# MISC.net
KiCad netlist of a schematic drawn in Altium Designer
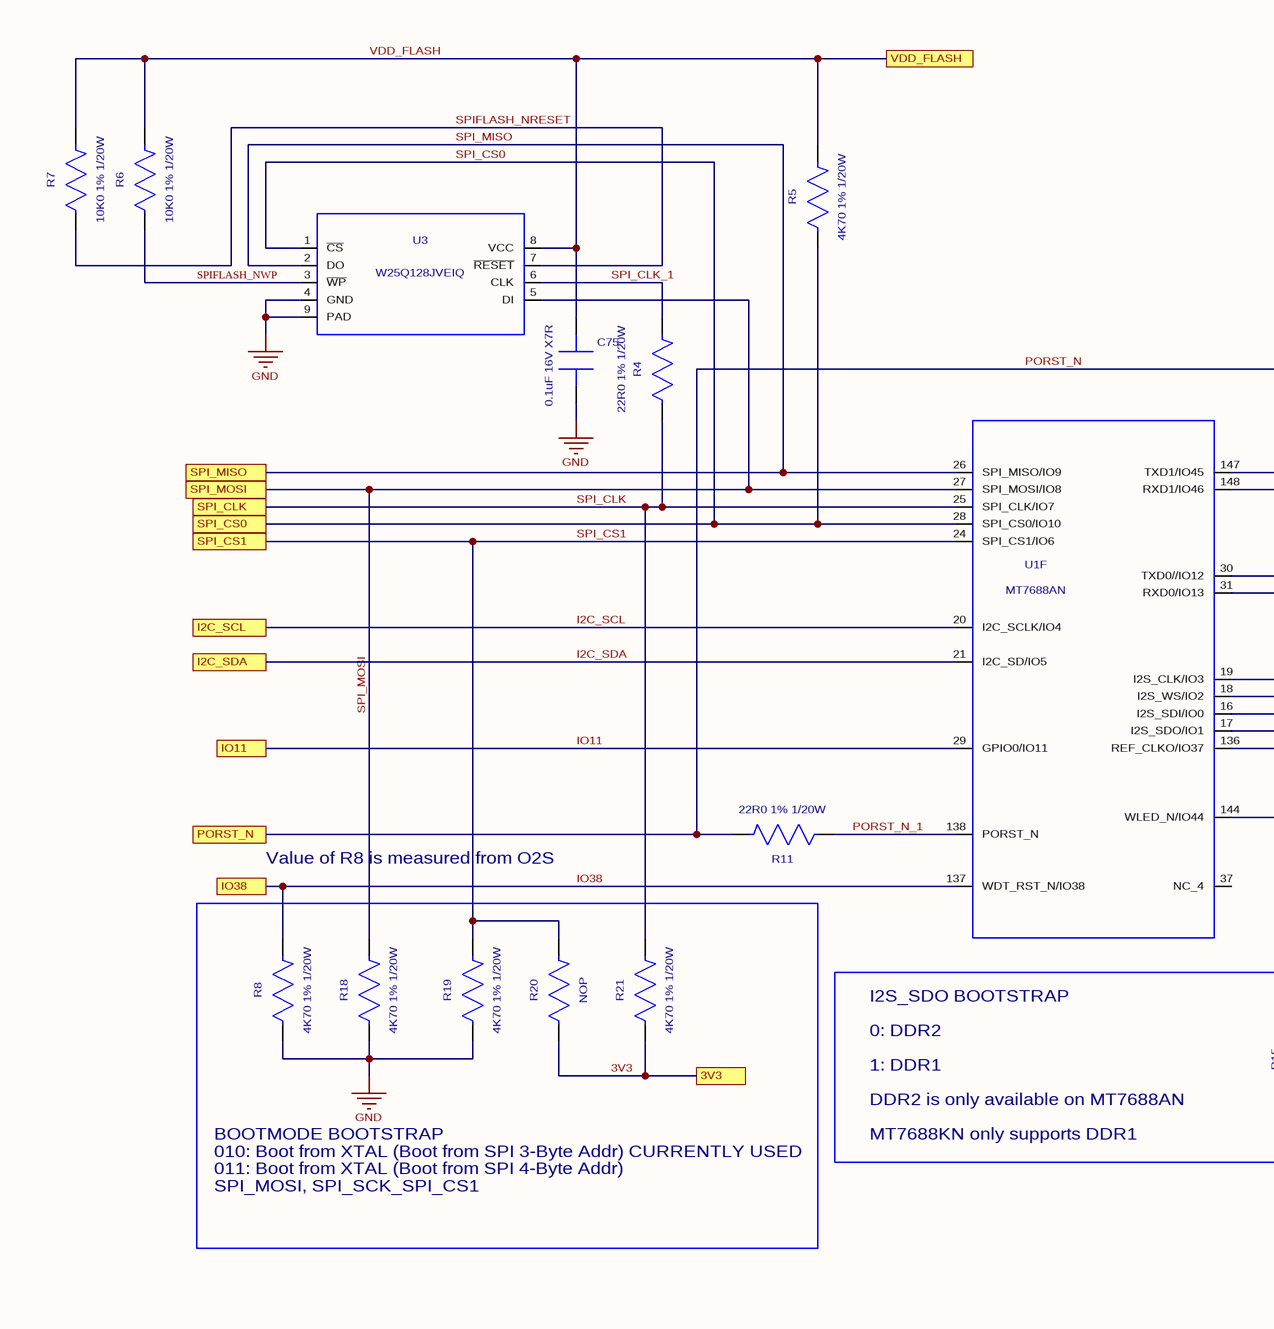
[diagram p0: MISC.SchDoc, left]
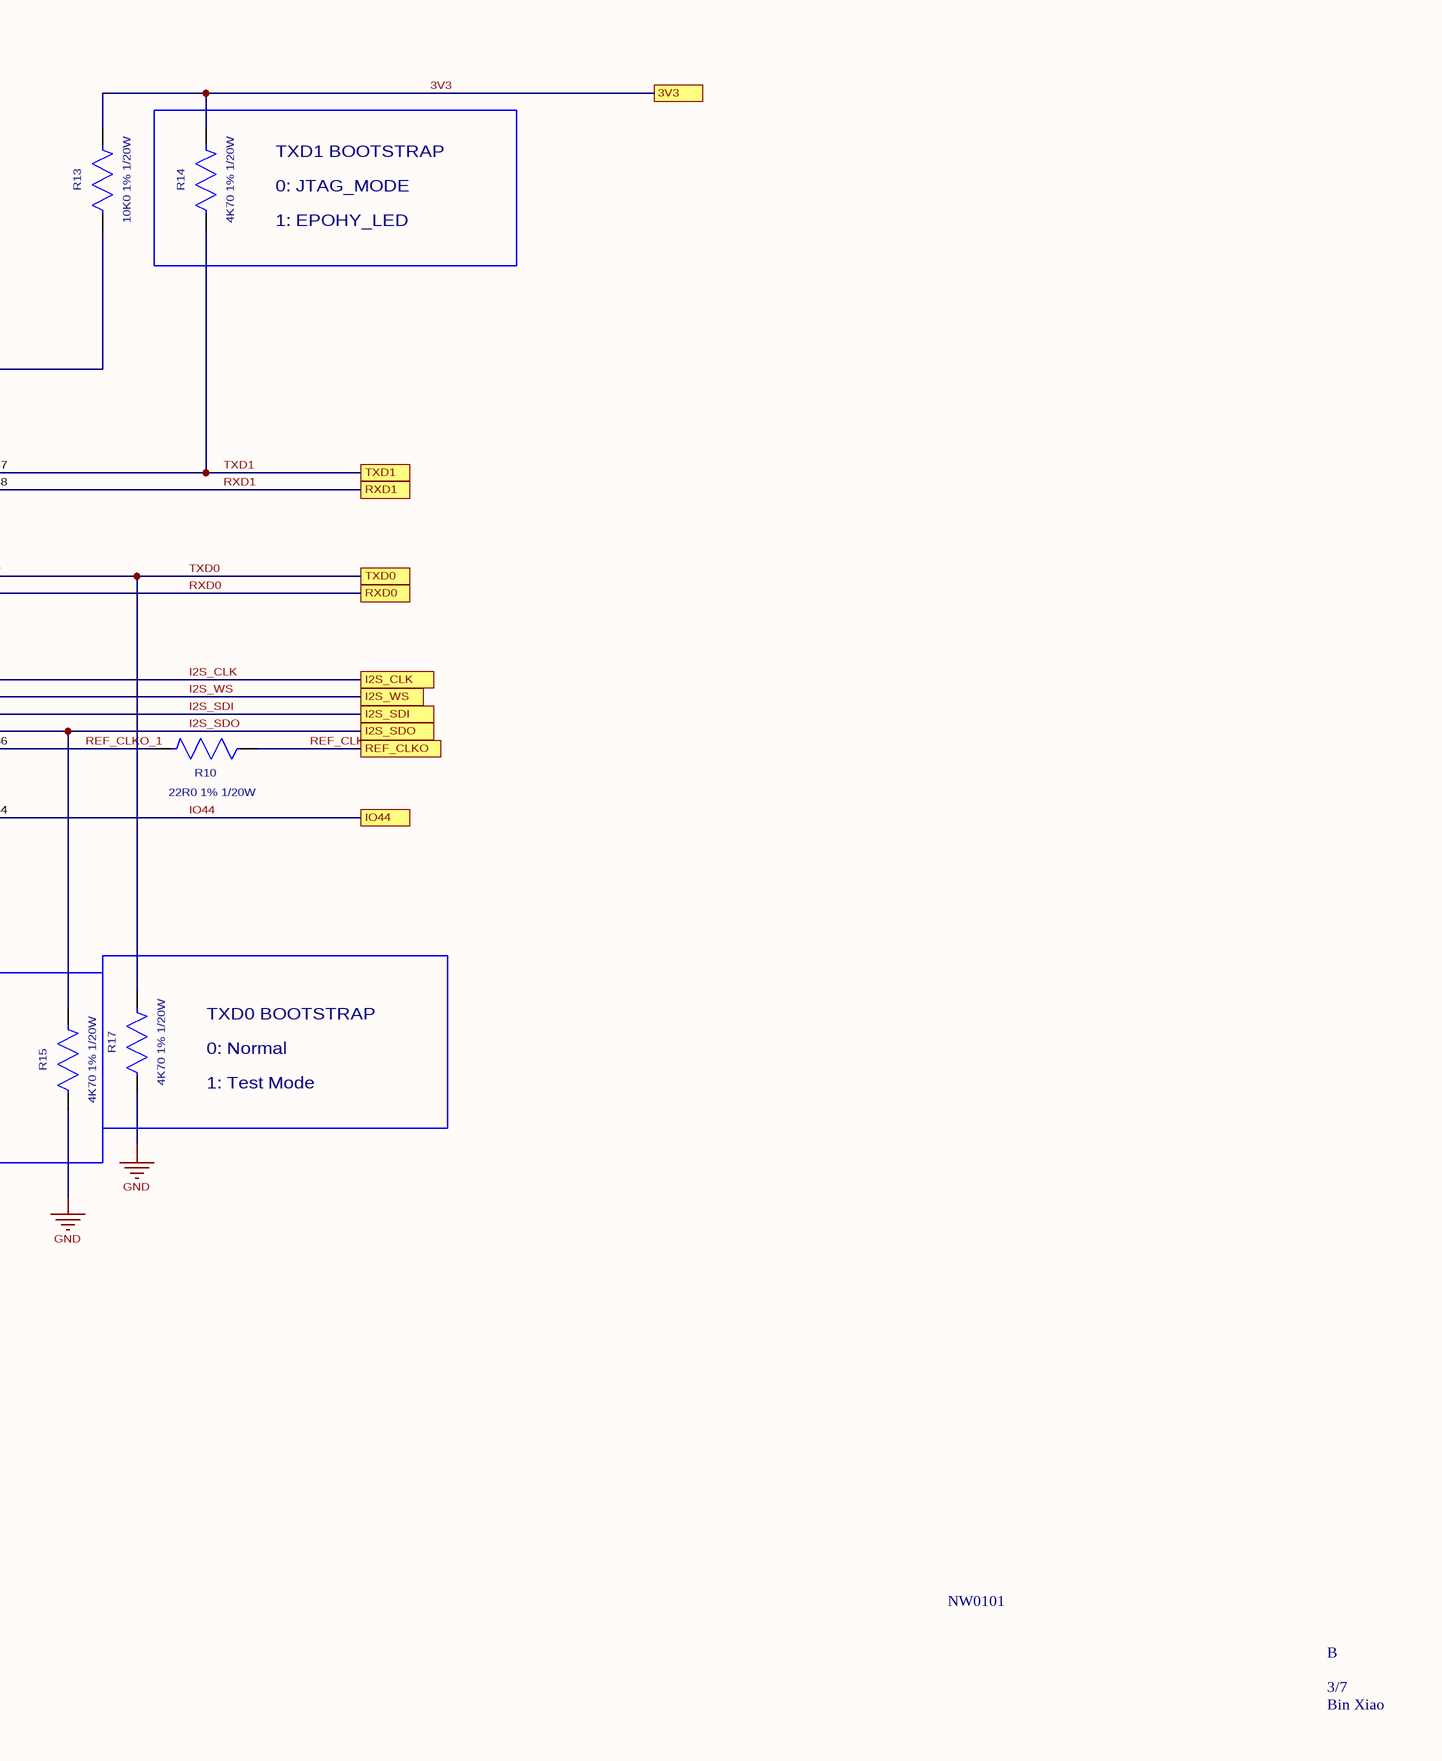
[diagram p1: MISC.SchDoc, right]

(export (version "E")
  (design (tool "Eeschema 10.0.6"))
  (components
    (comp (ref "C75")
      (value "0.1uF 16V X7R")
      (footprint "C0201")
      (description "CAP CER 0.1UF 16V X7R 0201")
      (fields
        (field (name "PART NUMBER") "GRM033Z71C104KE14D")
        (field (name "MANUFACTURER") "Murata Electronics")
      )
      (libsource (lib "NetworkModule") (part "CAP0201-104-16V-X7R"))
    )
    (comp (ref "R4")
      (value "22R0 1% 1/20W")
      (footprint "R0201")
      (description "RES 22 OHM 1% 1/20W 0201")
      (fields (field (name "MANUFACTURER") "Yageo") (field (name "PART NUMBER") "RC0201FR-0722RL"))
      (libsource (lib "NetworkModule") (part "RES0201-22R0"))
    )
    (comp (ref "R5")
      (value "4K70 1% 1/20W")
      (footprint "R0201")
      (description "RES 4.7K OHM 1% 1/20W 0201")
      (fields (field (name "MANUFACTURER") "Yageo") (field (name "PART NUMBER") "RC0201FR-074K7L"))
      (libsource (lib "NetworkModule") (part "RES0201-4K70"))
    )
    (comp (ref "R6")
      (value "10K0 1% 1/20W")
      (footprint "R0201")
      (description "RES SMD 10K OHM 1% 1/20W 0201")
      (fields (field (name "MANUFACTURER") "Yageo") (field (name "PART NUMBER") "RC0201FR-0710KP"))
      (libsource (lib "NetworkModule") (part "RES0201-10K0"))
    )
    (comp (ref "R7")
      (value "10K0 1% 1/20W")
      (footprint "R0201")
      (description "RES SMD 10K OHM 1% 1/20W 0201")
      (fields (field (name "MANUFACTURER") "Yageo") (field (name "PART NUMBER") "RC0201FR-0710KP"))
      (libsource (lib "NetworkModule") (part "RES0201-10K0"))
    )
    (comp (ref "R8")
      (value "4K70 1% 1/20W")
      (footprint "R0201")
      (description "RES 4.7K OHM 1% 1/20W 0201")
      (fields (field (name "MANUFACTURER") "Yageo") (field (name "PART NUMBER") "RC0201FR-074K7L"))
      (libsource (lib "NetworkModule") (part "RES0201-4K70"))
    )
    (comp (ref "R10")
      (value "22R0 1% 1/20W")
      (footprint "R0201")
      (description "RES 22 OHM 1% 1/20W 0201")
      (fields (field (name "MANUFACTURER") "Yageo") (field (name "PART NUMBER") "RC0201FR-0722RL"))
      (libsource (lib "NetworkModule") (part "RES0201-22R0"))
    )
    (comp (ref "R11")
      (value "22R0 1% 1/20W")
      (footprint "R0201")
      (description "RES 22 OHM 1% 1/20W 0201")
      (fields (field (name "MANUFACTURER") "Yageo") (field (name "PART NUMBER") "RC0201FR-0722RL"))
      (libsource (lib "NetworkModule") (part "RES0201-22R0"))
    )
    (comp (ref "R13")
      (value "10K0 1% 1/20W")
      (footprint "R0201")
      (description "RES SMD 10K OHM 1% 1/20W 0201")
      (fields (field (name "MANUFACTURER") "Yageo") (field (name "PART NUMBER") "RC0201FR-0710KP"))
      (libsource (lib "NetworkModule") (part "RES0201-10K0"))
    )
    (comp (ref "R14")
      (value "4K70 1% 1/20W")
      (footprint "R0201")
      (description "RES 4.7K OHM 1% 1/20W 0201")
      (fields (field (name "MANUFACTURER") "Yageo") (field (name "PART NUMBER") "RC0201FR-074K7L"))
      (libsource (lib "NetworkModule") (part "RES0201-4K70"))
    )
    (comp (ref "R15")
      (value "4K70 1% 1/20W")
      (footprint "R0201")
      (description "RES 4.7K OHM 1% 1/20W 0201")
      (fields (field (name "MANUFACTURER") "Yageo") (field (name "PART NUMBER") "RC0201FR-074K7L"))
      (libsource (lib "NetworkModule") (part "RES0201-4K70"))
    )
    (comp (ref "R17")
      (value "4K70 1% 1/20W")
      (footprint "R0201")
      (description "RES 4.7K OHM 1% 1/20W 0201")
      (fields (field (name "MANUFACTURER") "Yageo") (field (name "PART NUMBER") "RC0201FR-074K7L"))
      (libsource (lib "NetworkModule") (part "RES0201-4K70"))
    )
    (comp (ref "R18")
      (value "4K70 1% 1/20W")
      (footprint "R0201")
      (description "RES 4.7K OHM 1% 1/20W 0201")
      (fields (field (name "MANUFACTURER") "Yageo") (field (name "PART NUMBER") "RC0201FR-074K7L"))
      (libsource (lib "NetworkModule") (part "RES0201-4K70"))
    )
    (comp (ref "R19")
      (value "4K70 1% 1/20W")
      (footprint "R0201")
      (description "RES 4.7K OHM 1% 1/20W 0201")
      (fields (field (name "MANUFACTURER") "Yageo") (field (name "PART NUMBER") "RC0201FR-074K7L"))
      (libsource (lib "NetworkModule") (part "RES0201-4K70"))
    )
    (comp (ref "R20")
      (value "NOP")
      (footprint "R0201_NOP")
      (fields (field (name "Comment") "RES0201-NOP"))
      (libsource (lib "NetworkModule") (part "RES0201-NOP"))
    )
    (comp (ref "R21")
      (value "4K70 1% 1/20W")
      (footprint "R0201")
      (description "RES 4.7K OHM 1% 1/20W 0201")
      (fields (field (name "MANUFACTURER") "Yageo") (field (name "PART NUMBER") "RC0201FR-074K7L"))
      (libsource (lib "NetworkModule") (part "RES0201-4K70"))
    )
    (comp (ref "U1")
      (value "MT7688AN")
      (footprint "DR-QFN-128")
      (description "580Mhz 32bits Networking Processor")
      (fields (field (name "MANUFACTURER") "MediaTek Inc"))
      (libsource (lib "*") (part "MT7688AN"))
    )
    (comp (ref "U3")
      (value "W25Q128JVEIQ")
      (footprint "WIN_E-8_WIN")
      (description "IC FLASH 128MBIT SPI/QUAD 8WSON")
      (fields (field (name "MANUFACTURER") "Winbond Electronics"))
      (libsource (lib "NetworkModule") (part "W25Q128JVEIQ"))
    )
  )
  (nets
    (net (code "1") (name "/3V3") (class "Default")
      (node (ref "R13") (pin "2") (pinfunction "2_2") (pintype "passive"))
      (node (ref "R14") (pin "2") (pinfunction "2_2") (pintype "passive"))
      (node (ref "R20") (pin "1") (pinfunction "1_1") (pintype "passive"))
      (node (ref "R21") (pin "1") (pinfunction "1_1") (pintype "passive"))
    )
    (net (code "2") (name "/I2C_SCL") (class "Default")
      (node (ref "U1") (pin "20") (pinfunction "I2C_SCLK/IO4_20") (pintype "passive"))
    )
    (net (code "3") (name "/I2C_SDA") (class "Default")
      (node (ref "U1") (pin "21") (pinfunction "I2C_SD/IO5_21") (pintype "passive"))
    )
    (net (code "4") (name "/I2S_CLK") (class "Default")
      (node (ref "U1") (pin "19") (pinfunction "I2S_CLK/IO3_19") (pintype "passive"))
    )
    (net (code "5") (name "/I2S_SDI") (class "Default")
      (node (ref "U1") (pin "16") (pinfunction "I2S_SDI/IO0_16") (pintype "passive"))
    )
    (net (code "6") (name "/I2S_SDO") (class "Default")
      (node (ref "R15") (pin "2") (pinfunction "2_2") (pintype "passive"))
      (node (ref "U1") (pin "17") (pinfunction "I2S_SDO/IO1_17") (pintype "passive"))
    )
    (net (code "7") (name "/I2S_WS") (class "Default")
      (node (ref "U1") (pin "18") (pinfunction "I2S_WS/IO2_18") (pintype "passive"))
    )
    (net (code "8") (name "/IO11") (class "Default")
      (node (ref "U1") (pin "29") (pinfunction "GPIO0/IO11_29") (pintype "passive"))
    )
    (net (code "9") (name "/IO38") (class "Default")
      (node (ref "R8") (pin "2") (pinfunction "2_2") (pintype "passive"))
      (node (ref "U1") (pin "137") (pinfunction "WDT_RST_N/IO38_137") (pintype "passive"))
    )
    (net (code "10") (name "/IO44") (class "Default")
      (node (ref "U1") (pin "144") (pinfunction "WLED_N/IO44_144") (pintype "passive"))
    )
    (net (code "11") (name "/PORST_N") (class "Default")
      (node (ref "R11") (pin "2") (pinfunction "2_2") (pintype "passive"))
      (node (ref "R13") (pin "1") (pinfunction "1_1") (pintype "passive"))
    )
    (net (code "12") (name "/PORST_N_1") (class "Default")
      (node (ref "R11") (pin "1") (pinfunction "1_1") (pintype "passive"))
      (node (ref "U1") (pin "138") (pinfunction "PORST_N_138") (pintype "passive"))
    )
    (net (code "13") (name "/REF_CLKO") (class "Default")
      (node (ref "R10") (pin "1") (pinfunction "1_1") (pintype "passive"))
    )
    (net (code "14") (name "/REF_CLKO_1") (class "Default")
      (node (ref "R10") (pin "2") (pinfunction "2_2") (pintype "passive"))
      (node (ref "U1") (pin "136") (pinfunction "REF_CLKO/IO37_136") (pintype "passive"))
    )
    (net (code "15") (name "/RXD0") (class "Default")
      (node (ref "U1") (pin "31") (pinfunction "RXD0/IO13_31") (pintype "passive"))
    )
    (net (code "16") (name "/RXD1") (class "Default")
      (node (ref "U1") (pin "148") (pinfunction "RXD1/IO46_148") (pintype "passive"))
    )
    (net (code "17") (name "/SPIFLASH_NRESET") (class "Default")
      (node (ref "R7") (pin "1") (pinfunction "1_1") (pintype "passive"))
      (node (ref "U3") (pin "7") (pinfunction "RESET_7") (pintype "passive"))
    )
    (net (code "18") (name "/SPIFLASH_NWP") (class "Default")
      (node (ref "R6") (pin "1") (pinfunction "1_1") (pintype "passive"))
      (node (ref "U3") (pin "3") (pinfunction "WP_3") (pintype "passive"))
    )
    (net (code "19") (name "/SPI_CLK") (class "Default")
      (node (ref "R21") (pin "2") (pinfunction "2_2") (pintype "passive"))
      (node (ref "R4") (pin "1") (pinfunction "1_1") (pintype "passive"))
      (node (ref "U1") (pin "25") (pinfunction "SPI_CLK/IO7_25") (pintype "passive"))
    )
    (net (code "20") (name "/SPI_CLK_1") (class "Default")
      (node (ref "R4") (pin "2") (pinfunction "2_2") (pintype "passive"))
      (node (ref "U3") (pin "6") (pinfunction "CLK_6") (pintype "passive"))
    )
    (net (code "21") (name "/SPI_CS0") (class "Default")
      (node (ref "R5") (pin "1") (pinfunction "1_1") (pintype "passive"))
      (node (ref "U1") (pin "28") (pinfunction "SPI_CS0/IO10_28") (pintype "passive"))
      (node (ref "U3") (pin "1") (pinfunction "CS_1") (pintype "passive"))
    )
    (net (code "22") (name "/SPI_CS1") (class "Default")
      (node (ref "R19") (pin "2") (pinfunction "2_2") (pintype "passive"))
      (node (ref "R20") (pin "2") (pinfunction "2_2") (pintype "passive"))
      (node (ref "U1") (pin "24") (pinfunction "SPI_CS1/IO6_24") (pintype "passive"))
    )
    (net (code "23") (name "/SPI_MISO") (class "Default")
      (node (ref "U1") (pin "26") (pinfunction "SPI_MISO/IO9_26") (pintype "passive"))
      (node (ref "U3") (pin "2") (pinfunction "DO_2") (pintype "passive"))
    )
    (net (code "24") (name "/SPI_MOSI") (class "Default")
      (node (ref "R18") (pin "2") (pinfunction "2_2") (pintype "passive"))
      (node (ref "U1") (pin "27") (pinfunction "SPI_MOSI/IO8_27") (pintype "passive"))
      (node (ref "U3") (pin "5") (pinfunction "DI_5") (pintype "passive"))
    )
    (net (code "25") (name "/TXD0") (class "Default")
      (node (ref "R17") (pin "2") (pinfunction "2_2") (pintype "passive"))
      (node (ref "U1") (pin "30") (pinfunction "TXD0//IO12_30") (pintype "passive"))
    )
    (net (code "26") (name "/TXD1") (class "Default")
      (node (ref "R14") (pin "1") (pinfunction "1_1") (pintype "passive"))
      (node (ref "U1") (pin "147") (pinfunction "TXD1/IO45_147") (pintype "passive"))
    )
    (net (code "27") (name "/VDD_FLASH") (class "Default")
      (node (ref "C75") (pin "1") (pinfunction "1_1") (pintype "passive"))
      (node (ref "R5") (pin "2") (pinfunction "2_2") (pintype "passive"))
      (node (ref "R6") (pin "2") (pinfunction "2_2") (pintype "passive"))
      (node (ref "R7") (pin "2") (pinfunction "2_2") (pintype "passive"))
      (node (ref "U3") (pin "8") (pinfunction "VCC_8") (pintype "passive"))
    )
    (net (code "28") (name "GND") (class "Default")
      (node (ref "C75") (pin "2") (pinfunction "2_2") (pintype "passive"))
      (node (ref "R15") (pin "1") (pinfunction "1_1") (pintype "passive"))
      (node (ref "R17") (pin "1") (pinfunction "1_1") (pintype "passive"))
      (node (ref "R18") (pin "1") (pinfunction "1_1") (pintype "passive"))
      (node (ref "R19") (pin "1") (pinfunction "1_1") (pintype "passive"))
      (node (ref "R8") (pin "1") (pinfunction "1_1") (pintype "passive"))
      (node (ref "U3") (pin "4") (pinfunction "GND_4") (pintype "passive"))
      (node (ref "U3") (pin "9") (pinfunction "PAD_9") (pintype "passive"))
    )
    (net (code "29") (name "unconnected-(U1F-NC_4-Pad37)") (class "Default")
      (node (ref "U1") (pin "37") (pinfunction "NC_4_37") (pintype "passive"))
    )
  )
)
